# ModuleCarrier.net
KiCad netlist of a schematic drawn in Altium Designer
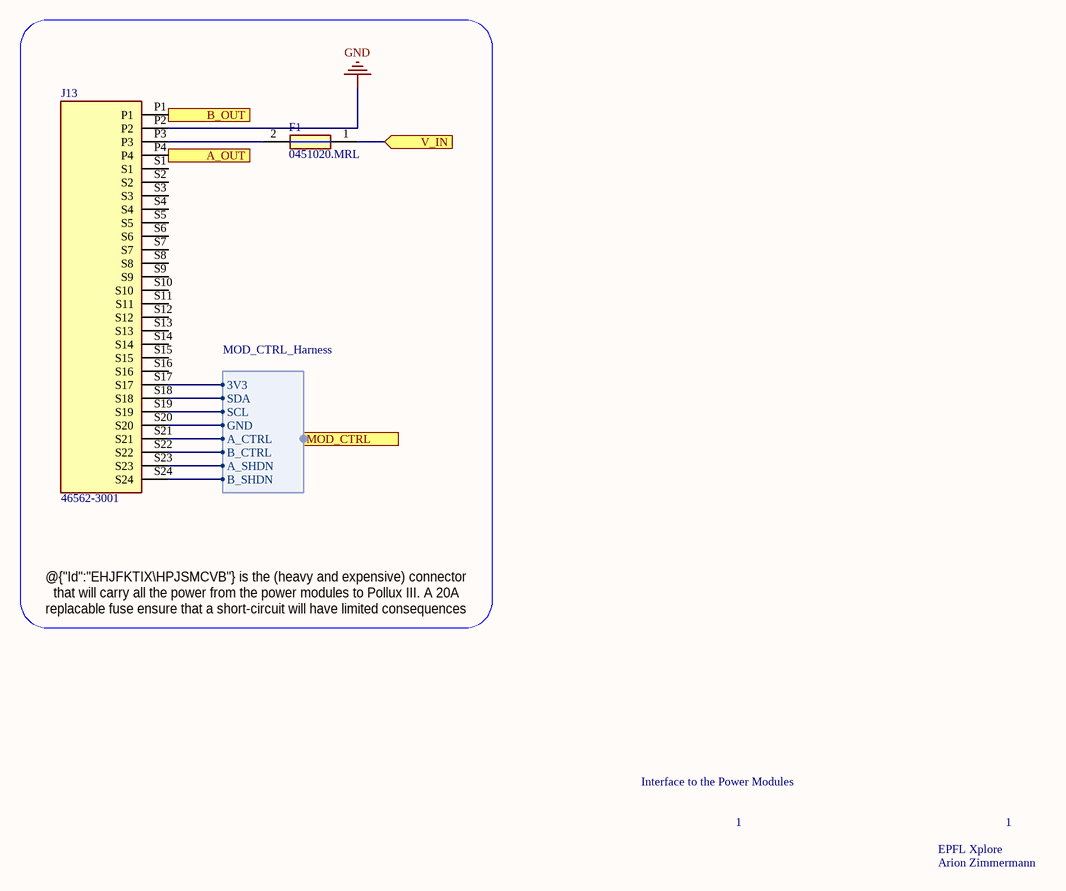
[diagram p0: ModuleCarrier.SchDoc]

(export (version "E")
  (design (tool "Eeschema 10.0.6"))
  (components
    (comp (ref "F1")
      (value "0451020.MRL")
      (footprint "SamacSys:FUSC6127X294N")
      (description "Fuse")
      (fields (field (name "MOUSER PART NUMBER") "576-0451020.MRL"))
      (libsource (lib "SamacSys") (part "0451020.MRL"))
    )
    (comp (ref "J13")
      (value "46562-3001")
      (footprint "465623001")
      (description "Connector")
      (libsource (lib "SamacSys") (part "46562-3001"))
    )
  )
  (nets
    (net (code "2") (name "/3V3") (class "Default")
      (node (ref "J13") (pin "S17") (pinfunction "S17_S17") (pintype "passive"))
    )
    (net (code "3") (name "/A_CTRL") (class "Default")
      (node (ref "J13") (pin "S21") (pinfunction "S21_S21") (pintype "passive"))
    )
    (net (code "4") (name "/A_OUT") (class "Default")
      (node (ref "J13") (pin "P4") (pinfunction "P4_P4") (pintype "passive"))
    )
    (net (code "5") (name "/A_SHDN") (class "Default")
      (node (ref "J13") (pin "S23") (pinfunction "S23_S23") (pintype "passive"))
    )
    (net (code "6") (name "/B_CTRL") (class "Default")
      (node (ref "J13") (pin "S22") (pinfunction "S22_S22") (pintype "passive"))
    )
    (net (code "7") (name "/B_OUT") (class "Default")
      (node (ref "J13") (pin "P1") (pinfunction "P1_P1") (pintype "passive"))
    )
    (net (code "8") (name "/B_SHDN") (class "Default")
      (node (ref "J13") (pin "S24") (pinfunction "S24_S24") (pintype "passive"))
    )
    (net (code "9") (name "/SCL") (class "Default")
      (node (ref "J13") (pin "S19") (pinfunction "S19_S19") (pintype "passive"))
    )
    (net (code "10") (name "/SDA") (class "Default")
      (node (ref "J13") (pin "S18") (pinfunction "S18_S18") (pintype "passive"))
    )
    (net (code "11") (name "/V_IN") (class "Default")
      (node (ref "F1") (pin "1") (pinfunction "1_1") (pintype "passive"))
    )
    (net (code "13") (name "GND") (class "Default")
      (node (ref "J13") (pin "P2") (pinfunction "P2_P2") (pintype "passive"))
    )
    (net (code "14") (name "Net-(F1-Pad2)") (class "Default")
      (node (ref "F1") (pin "2") (pinfunction "2_2") (pintype "passive"))
      (node (ref "J13") (pin "P3") (pinfunction "P3_P3") (pintype "passive"))
    )
    (net (code "15") (name "unconnected-(J13-PadS1)") (class "Default")
      (node (ref "J13") (pin "S1") (pinfunction "S1_S1") (pintype "passive"))
    )
    (net (code "16") (name "unconnected-(J13-PadS2)") (class "Default")
      (node (ref "J13") (pin "S2") (pinfunction "S2_S2") (pintype "passive"))
    )
    (net (code "17") (name "unconnected-(J13-PadS3)") (class "Default")
      (node (ref "J13") (pin "S3") (pinfunction "S3_S3") (pintype "passive"))
    )
    (net (code "18") (name "unconnected-(J13-PadS4)") (class "Default")
      (node (ref "J13") (pin "S4") (pinfunction "S4_S4") (pintype "passive"))
    )
    (net (code "19") (name "unconnected-(J13-PadS5)") (class "Default")
      (node (ref "J13") (pin "S5") (pinfunction "S5_S5") (pintype "passive"))
    )
    (net (code "20") (name "unconnected-(J13-PadS6)") (class "Default")
      (node (ref "J13") (pin "S6") (pinfunction "S6_S6") (pintype "passive"))
    )
    (net (code "21") (name "unconnected-(J13-PadS7)") (class "Default")
      (node (ref "J13") (pin "S7") (pinfunction "S7_S7") (pintype "passive"))
    )
    (net (code "22") (name "unconnected-(J13-PadS8)") (class "Default")
      (node (ref "J13") (pin "S8") (pinfunction "S8_S8") (pintype "passive"))
    )
    (net (code "23") (name "unconnected-(J13-PadS9)") (class "Default")
      (node (ref "J13") (pin "S9") (pinfunction "S9_S9") (pintype "passive"))
    )
    (net (code "24") (name "unconnected-(J13-PadS10)") (class "Default")
      (node (ref "J13") (pin "S10") (pinfunction "S10_S10") (pintype "passive"))
    )
    (net (code "25") (name "unconnected-(J13-PadS11)") (class "Default")
      (node (ref "J13") (pin "S11") (pinfunction "S11_S11") (pintype "passive"))
    )
    (net (code "26") (name "unconnected-(J13-PadS12)") (class "Default")
      (node (ref "J13") (pin "S12") (pinfunction "S12_S12") (pintype "passive"))
    )
    (net (code "27") (name "unconnected-(J13-PadS13)") (class "Default")
      (node (ref "J13") (pin "S13") (pinfunction "S13_S13") (pintype "passive"))
    )
    (net (code "28") (name "unconnected-(J13-PadS14)") (class "Default")
      (node (ref "J13") (pin "S14") (pinfunction "S14_S14") (pintype "passive"))
    )
    (net (code "29") (name "unconnected-(J13-PadS15)") (class "Default")
      (node (ref "J13") (pin "S15") (pinfunction "S15_S15") (pintype "passive"))
    )
    (net (code "30") (name "unconnected-(J13-PadS16)") (class "Default")
      (node (ref "J13") (pin "S16") (pinfunction "S16_S16") (pintype "passive"))
    )
    (net (code "31") (name "unconnected-(J13-PadS20)") (class "Default")
      (node (ref "J13") (pin "S20") (pinfunction "S20_S20") (pintype "passive"))
    )
  )
)
